# hv_bleed.net
KiCad netlist of a schematic drawn in Altium Designer
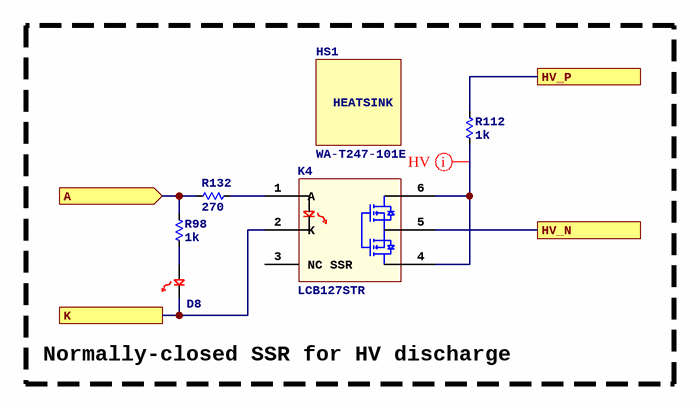
[diagram p0: hv_bleed.SchDoc]

(export (version "E")
  (design (tool "Eeschema 10.0.6"))
  (components
    (comp (ref "D8")
      (value "LTST-C190KRKT")
      (footprint "LED_0603P_RED")
      (description "LED SUPER RED CLEAR 0603 SMD")
      (fields (field (name "MANUFACTURER") "Lite-On Inc"))
      (libsource (lib "database") (part "__template_led_red"))
    )
    (comp (ref "HS1")
      (value "WA-T247-101E")
      (footprint "OHMITE_WA-T247-101E")
      (description "Heat Sink, 11ohm, Extruded, Clip, Longitudinal, Aluminum Alloy, Anodized")
      (fields (field (name "MANUFACTURER") "Ohmite"))
      (libsource (lib "database") (part "WA-T247-101E"))
    )
    (comp (ref "K4")
      (value "LCB127STR")
      (footprint "6SMD300")
      (description "Relay Ssr 50MA 1.4V Dc-in 0.2A 250V Ac/dc-out 6-PIN PDIP SMD T/r")
      (fields (field (name "MANUFACTURER") "IXYS"))
      (libsource (lib "database") (part "LCB127STR"))
    )
    (comp (ref "R98")
      (value "1k")
      (footprint "R0402")
      (fields
        (field (name "TOLERANCE") "1%")
        (field (name "MANUFACTURER PART NUMBER") "0402WGF1001TCE")
        (field (name "MANUFACTURER") "UNI-ROYAL(Uniroyal Elec)")
      )
      (libsource (lib "database") (part "__template_resistor"))
    )
    (comp (ref "R112")
      (value "1k")
      (footprint "TO-247-2_VERTICAL")
      (fields
        (field (name "MANUFACTURER") "Ohmite")
        (field (name "MANUFACTURER PART NUMBER") "TEH100M1K00JE")
        (field (name "TOLERANCE") "5%")
      )
      (libsource (lib "database") (part "__template_resistor"))
    )
    (comp (ref "R132")
      (value "270")
      (footprint "R0402")
      (fields
        (field (name "TOLERANCE") "1%")
        (field (name "MANUFACTURER PART NUMBER") "0402WGF2700TCE")
        (field (name "MANUFACTURER") "UNI-ROYAL(Uniroyal Elec)")
      )
      (libsource (lib "database") (part "__template_resistor"))
    )
  )
  (nets
    (net (code "1") (name "/A") (class "Default")
      (node (ref "R132") (pin "2") (pintype "passive"))
      (node (ref "R98") (pin "1") (pintype "passive"))
    )
    (net (code "2") (name "/HV_N") (class "Default") (node (ref "K4") (pin "5") (pintype "passive")))
    (net (code "3") (name "/HV_P") (class "Default") (node (ref "R112") (pin "2") (pintype "passive")))
    (net (code "4") (name "/K") (class "Default")
      (node (ref "D8") (pin "2") (pintype "passive"))
      (node (ref "K4") (pin "2") (pinfunction "K_2") (pintype "passive"))
    )
    (net (code "5") (name "Net-(D8-Pad1)") (class "Default")
      (node (ref "D8") (pin "1") (pintype "passive"))
      (node (ref "R98") (pin "2") (pintype "passive"))
    )
    (net (code "6") (name "Net-(K4-A)") (class "Default")
      (node (ref "K4") (pin "1") (pinfunction "A_1") (pintype "passive"))
      (node (ref "R132") (pin "1") (pintype "passive"))
    )
    (net (code "7") (name "Net-(K4-Pad4)") (class "Default")
      (node (ref "K4") (pin "4") (pintype "passive"))
      (node (ref "K4") (pin "6") (pintype "passive"))
      (node (ref "R112") (pin "1") (pintype "passive"))
    )
    (net (code "8") (name "unconnected-(K4-Pad3)") (class "Default")
      (node (ref "K4") (pin "3") (pintype "passive"))
    )
  )
)
